# LED_bars.net
KiCad netlist of a schematic drawn in Altium Designer
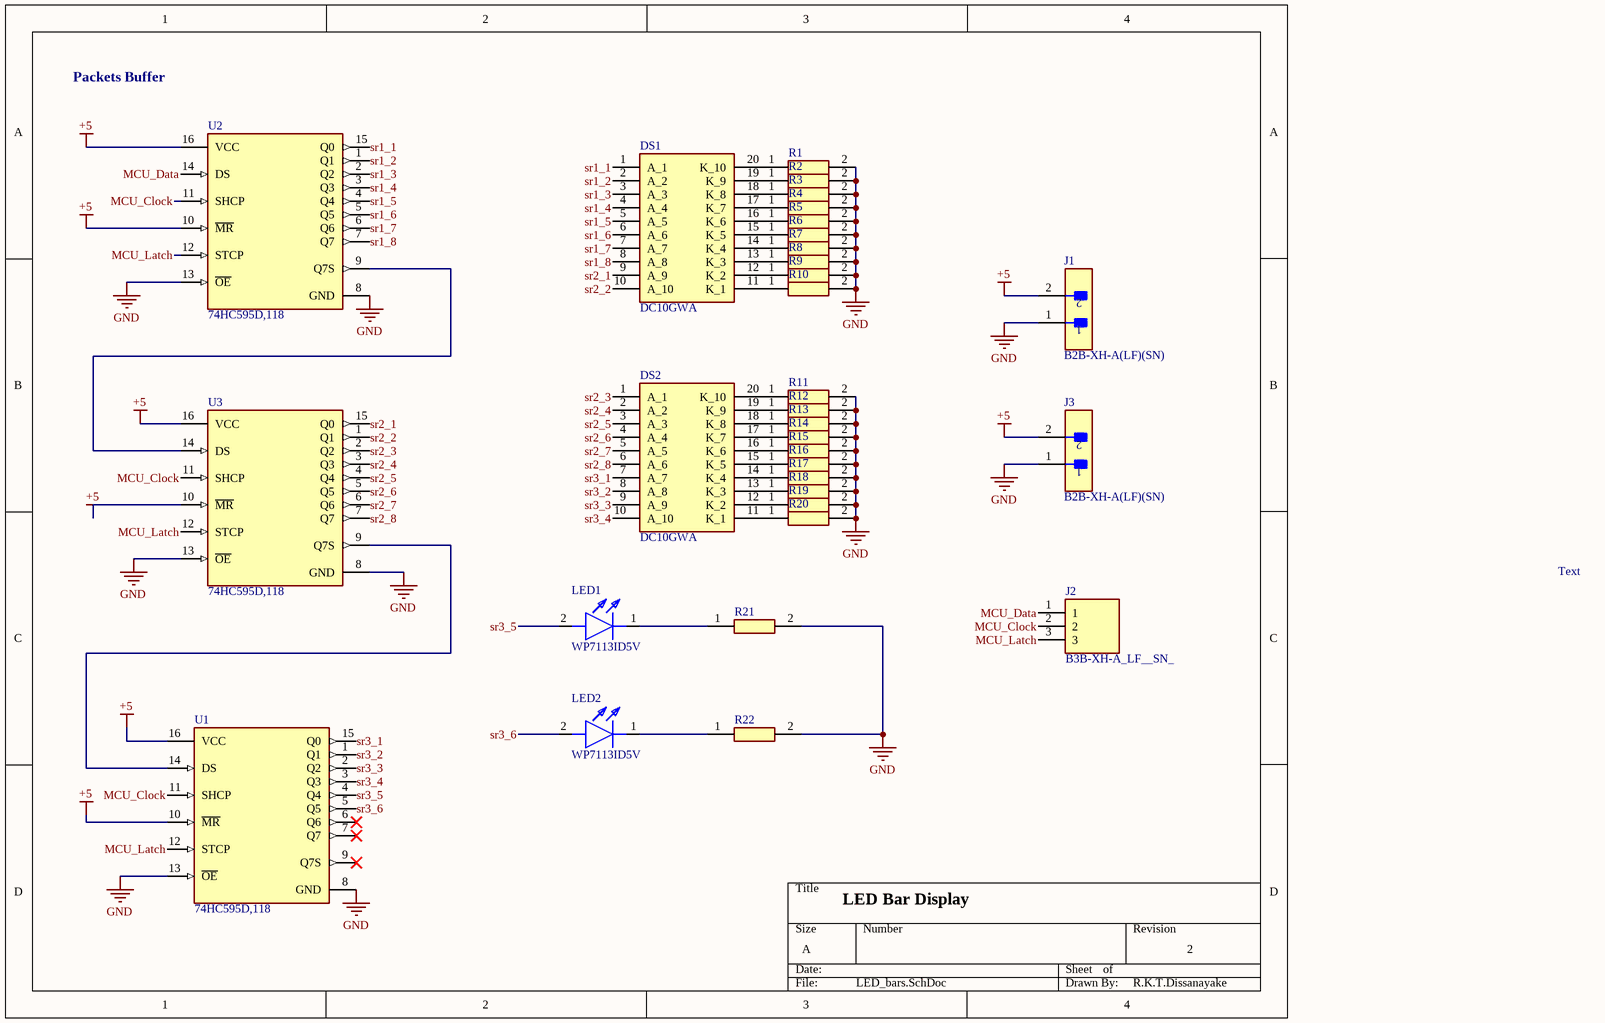
[diagram p0: LED_bars.SchDoc]

(export (version "E")
  (design (tool "Eeschema 10.0.6"))
  (components
    (comp (ref "DS1")
      (value "DC10GWA")
      (footprint "LED_Buffer:DIPS750W75P254L2540H825Q20N")
      (description "Display")
      (fields (field (name "MOUSER PART NUMBER") "604-DC10GWA"))
      (libsource (lib "*") (part "DC10GWA"))
    )
    (comp (ref "DS2")
      (value "DC10GWA")
      (footprint "LED_Buffer:DIPS750W75P254L2540H825Q20N")
      (description "Display")
      (fields (field (name "MOUSER PART NUMBER") "604-DC10GWA"))
      (libsource (lib "*") (part "DC10GWA"))
    )
    (comp (ref "J1")
      (value "B2B-XH-A(LF)(SN)")
      (footprint "FP-B2B-XH-A_LF_SN-MFG")
      (description "CONN HEADER VERT 2POS 2.5MM")
      (libsource (lib "Altium Content Vault") (part "3bc925449376181038e59eaffc5286c"))
    )
    (comp (ref "J2")
      (value "B3B-XH-A_LF__SN_")
      (footprint "LED_Buffer:B3BXHALFSN")
      (description "Connector")
      (fields
        (field (name "MANUFACTURER_PART_NUMBER") "B3B-XH-A(LF)(SN)")
        (field (name "MOUSER PART NUMBER") "306-B3BXHALFSNP")
      )
      (libsource (lib "*") (part "B3B-XH-A_LF__SN_"))
    )
    (comp (ref "J3")
      (value "B2B-XH-A(LF)(SN)")
      (footprint "FP-B2B-XH-A_LF_SN-MFG")
      (description "CONN HEADER VERT 2POS 2.5MM")
      (libsource (lib "Altium Content Vault") (part "3bc925449376181038e59eaffc5286c"))
    )
    (comp (ref "LED1")
      (value "WP7113ID5V")
      (footprint "LED_TwoBars:WP7113ID5V")
      (description "LED")
      (fields (field (name "MOUSER PART NUMBER") "604-WP7113ID5V"))
      (libsource (lib "*") (part "WP7113ID5V"))
    )
    (comp (ref "LED2")
      (value "WP7113ID5V")
      (footprint "LED_TwoBars:WP7113ID5V")
      (description "LED")
      (fields (field (name "MOUSER PART NUMBER") "604-WP7113ID5V"))
      (libsource (lib "*") (part "WP7113ID5V"))
    )
    (comp (ref "R1")
      (value "330")
      (footprint "LED_Buffer:RESC3126X65N")
      (description "Resistor")
      (fields (field (name "MANUFACTURER_PART_NUMBER") "RC1210FR-07330RL"))
      (libsource (lib "*") (part "RC1210FR-07330RL"))
    )
    (comp (ref "R2")
      (value "RC1210FR-07330RL")
      (footprint "LED_Buffer:RESC3126X65N")
      (description "Resistor")
      (libsource (lib "*") (part "RC1210FR-07330RL"))
    )
    (comp (ref "R3")
      (value "330")
      (footprint "LED_Buffer:RESC3126X65N")
      (description "Resistor")
      (fields (field (name "MANUFACTURER_PART_NUMBER") "RC1210FR-07330RL"))
      (libsource (lib "*") (part "RC1210FR-07330RL"))
    )
    (comp (ref "R4")
      (value "RC1210FR-07330RL")
      (footprint "LED_Buffer:RESC3126X65N")
      (description "Resistor")
      (libsource (lib "*") (part "RC1210FR-07330RL"))
    )
    (comp (ref "R5")
      (value "330")
      (footprint "LED_Buffer:RESC3126X65N")
      (description "Resistor")
      (fields (field (name "MANUFACTURER_PART_NUMBER") "RC1210FR-07330RL"))
      (libsource (lib "*") (part "RC1210FR-07330RL"))
    )
    (comp (ref "R6")
      (value "RC1210FR-07330RL")
      (footprint "LED_Buffer:RESC3126X65N")
      (description "Resistor")
      (libsource (lib "*") (part "RC1210FR-07330RL"))
    )
    (comp (ref "R7")
      (value "330")
      (footprint "LED_Buffer:RESC3126X65N")
      (description "Resistor")
      (fields (field (name "MANUFACTURER_PART_NUMBER") "RC1210FR-07330RL"))
      (libsource (lib "*") (part "RC1210FR-07330RL"))
    )
    (comp (ref "R8")
      (value "RC1210FR-07330RL")
      (footprint "LED_Buffer:RESC3126X65N")
      (description "Resistor")
      (libsource (lib "*") (part "RC1210FR-07330RL"))
    )
    (comp (ref "R9")
      (value "330")
      (footprint "LED_Buffer:RESC3126X65N")
      (description "Resistor")
      (fields (field (name "MANUFACTURER_PART_NUMBER") "RC1210FR-07330RL"))
      (libsource (lib "*") (part "RC1210FR-07330RL"))
    )
    (comp (ref "R10")
      (value "330")
      (footprint "LED_Buffer:RESC3126X65N")
      (description "Resistor")
      (fields (field (name "MANUFACTURER_PART_NUMBER") "RC1210FR-07330RL"))
      (libsource (lib "*") (part "RC1210FR-07330RL"))
    )
    (comp (ref "R11")
      (value "330")
      (footprint "LED_Buffer:RESC3126X65N")
      (description "Resistor")
      (fields (field (name "MANUFACTURER_PART_NUMBER") "RC1210FR-07330RL"))
      (libsource (lib "*") (part "RC1210FR-07330RL"))
    )
    (comp (ref "R12")
      (value "330")
      (footprint "LED_Buffer:RESC3126X65N")
      (description "Resistor")
      (fields (field (name "MANUFACTURER_PART_NUMBER") "RC1210FR-07330RL"))
      (libsource (lib "*") (part "RC1210FR-07330RL"))
    )
    (comp (ref "R13")
      (value "330")
      (footprint "LED_Buffer:RESC3126X65N")
      (description "Resistor")
      (fields (field (name "MANUFACTURER_PART_NUMBER") "RC1210FR-07330RL"))
      (libsource (lib "*") (part "RC1210FR-07330RL"))
    )
    (comp (ref "R14")
      (value "330")
      (footprint "LED_Buffer:RESC3126X65N")
      (description "Resistor")
      (fields (field (name "MANUFACTURER_PART_NUMBER") "RC1210FR-07330RL"))
      (libsource (lib "*") (part "RC1210FR-07330RL"))
    )
    (comp (ref "R15")
      (value "330")
      (footprint "LED_Buffer:RESC3126X65N")
      (description "Resistor")
      (fields (field (name "MANUFACTURER_PART_NUMBER") "RC1210FR-07330RL"))
      (libsource (lib "*") (part "RC1210FR-07330RL"))
    )
    (comp (ref "R16")
      (value "330")
      (footprint "LED_Buffer:RESC3126X65N")
      (description "Resistor")
      (fields (field (name "MANUFACTURER_PART_NUMBER") "RC1210FR-07330RL"))
      (libsource (lib "*") (part "RC1210FR-07330RL"))
    )
    (comp (ref "R17")
      (value "330")
      (footprint "LED_Buffer:RESC3126X65N")
      (description "Resistor")
      (fields (field (name "MANUFACTURER_PART_NUMBER") "RC1210FR-07330RL"))
      (libsource (lib "*") (part "RC1210FR-07330RL"))
    )
    (comp (ref "R18")
      (value "330")
      (footprint "LED_Buffer:RESC3126X65N")
      (description "Resistor")
      (fields (field (name "MANUFACTURER_PART_NUMBER") "RC1210FR-07330RL"))
      (libsource (lib "*") (part "RC1210FR-07330RL"))
    )
    (comp (ref "R19")
      (value "RC1210FR-07330RL")
      (footprint "LED_Buffer:RESC3126X65N")
      (description "Resistor")
      (libsource (lib "*") (part "RC1210FR-07330RL"))
    )
    (comp (ref "R20")
      (value "330")
      (footprint "LED_Buffer:RESC3126X65N")
      (description "Resistor")
      (fields (field (name "MANUFACTURER_PART_NUMBER") "RC1210FR-07330RL"))
      (libsource (lib "*") (part "RC1210FR-07330RL"))
    )
    (comp (ref "R21")
      (value "330")
      (footprint "LED_Buffer:RESC3126X65N")
      (description "Resistor")
      (fields (field (name "MANUFACTURER_PART_NUMBER") "RC1210FR-07330RL"))
      (libsource (lib "*") (part "RC1210FR-07330RL"))
    )
    (comp (ref "R22")
      (value "330")
      (footprint "LED_Buffer:RESC3126X65N")
      (description "Resistor")
      (fields (field (name "MANUFACTURER_PART_NUMBER") "RC1210FR-07330RL"))
      (libsource (lib "*") (part "RC1210FR-07330RL"))
    )
    (comp (ref "U1")
      (value "74HC595D,118")
      (footprint "FP-SOT109-1-IPC_C")
      (description "IC SHIFT REGISTER 8BIT 16SOIC")
      (libsource (lib "Altium Content Vault") (part "7b153f231cfcc3ac06dee253bd56617"))
    )
    (comp (ref "U2")
      (value "74HC595D,118")
      (footprint "FP-SOT109-1-IPC_C")
      (description "IC SHIFT REGISTER 8BIT 16SOIC")
      (libsource (lib "Altium Content Vault") (part "7b153f231cfcc3ac06dee253bd56617"))
    )
    (comp (ref "U3")
      (value "74HC595D,118")
      (footprint "FP-SOT109-1-IPC_C")
      (description "IC SHIFT REGISTER 8BIT 16SOIC")
      (libsource (lib "Altium Content Vault") (part "7b153f231cfcc3ac06dee253bd56617"))
    )
  )
  (nets
    (net (code "1") (name "+5") (class "Default")
      (node (ref "J1") (pin "2") (pinfunction "2_2") (pintype "passive"))
      (node (ref "J3") (pin "2") (pinfunction "2_2") (pintype "passive"))
      (node (ref "U1") (pin "10") (pinfunction "~{MR}_10") (pintype "input"))
      (node (ref "U1") (pin "16") (pinfunction "VCC_16") (pintype "power_in"))
      (node (ref "U2") (pin "10") (pinfunction "~{MR}_10") (pintype "input"))
      (node (ref "U2") (pin "16") (pinfunction "VCC_16") (pintype "power_in"))
      (node (ref "U3") (pin "10") (pinfunction "~{MR}_10") (pintype "input"))
      (node (ref "U3") (pin "16") (pinfunction "VCC_16") (pintype "power_in"))
    )
    (net (code "2") (name "/MCU_Clock") (class "Default")
      (node (ref "J2") (pin "2") (pinfunction "2_2") (pintype "passive"))
      (node (ref "U1") (pin "11") (pinfunction "SHCP_11") (pintype "input"))
      (node (ref "U2") (pin "11") (pinfunction "SHCP_11") (pintype "input"))
      (node (ref "U3") (pin "11") (pinfunction "SHCP_11") (pintype "input"))
    )
    (net (code "3") (name "/MCU_Data") (class "Default")
      (node (ref "J2") (pin "1") (pinfunction "1_1") (pintype "passive"))
      (node (ref "U2") (pin "14") (pinfunction "DS_14") (pintype "input"))
    )
    (net (code "4") (name "/MCU_Latch") (class "Default")
      (node (ref "J2") (pin "3") (pinfunction "3_3") (pintype "passive"))
      (node (ref "U1") (pin "12") (pinfunction "STCP_12") (pintype "input"))
      (node (ref "U2") (pin "12") (pinfunction "STCP_12") (pintype "input"))
      (node (ref "U3") (pin "12") (pinfunction "STCP_12") (pintype "input"))
    )
    (net (code "5") (name "/sr1_1") (class "Default")
      (node (ref "DS1") (pin "1") (pinfunction "A_1_1") (pintype "passive"))
      (node (ref "U2") (pin "15") (pinfunction "Q0_15") (pintype "output"))
    )
    (net (code "6") (name "/sr1_2") (class "Default")
      (node (ref "DS1") (pin "2") (pinfunction "A_2_2") (pintype "passive"))
      (node (ref "U2") (pin "1") (pinfunction "Q1_1") (pintype "output"))
    )
    (net (code "7") (name "/sr1_3") (class "Default")
      (node (ref "DS1") (pin "3") (pinfunction "A_3_3") (pintype "passive"))
      (node (ref "U2") (pin "2") (pinfunction "Q2_2") (pintype "output"))
    )
    (net (code "8") (name "/sr1_4") (class "Default")
      (node (ref "DS1") (pin "4") (pinfunction "A_4_4") (pintype "passive"))
      (node (ref "U2") (pin "3") (pinfunction "Q3_3") (pintype "output"))
    )
    (net (code "9") (name "/sr1_5") (class "Default")
      (node (ref "DS1") (pin "5") (pinfunction "A_5_5") (pintype "passive"))
      (node (ref "U2") (pin "4") (pinfunction "Q4_4") (pintype "output"))
    )
    (net (code "10") (name "/sr1_6") (class "Default")
      (node (ref "DS1") (pin "6") (pinfunction "A_6_6") (pintype "passive"))
      (node (ref "U2") (pin "5") (pinfunction "Q5_5") (pintype "output"))
    )
    (net (code "11") (name "/sr1_7") (class "Default")
      (node (ref "DS1") (pin "7") (pinfunction "A_7_7") (pintype "passive"))
      (node (ref "U2") (pin "6") (pinfunction "Q6_6") (pintype "output"))
    )
    (net (code "12") (name "/sr1_8") (class "Default")
      (node (ref "DS1") (pin "8") (pinfunction "A_8_8") (pintype "passive"))
      (node (ref "U2") (pin "7") (pinfunction "Q7_7") (pintype "output"))
    )
    (net (code "13") (name "/sr2_1") (class "Default")
      (node (ref "DS1") (pin "9") (pinfunction "A_9_9") (pintype "passive"))
      (node (ref "U3") (pin "15") (pinfunction "Q0_15") (pintype "output"))
    )
    (net (code "14") (name "/sr2_2") (class "Default")
      (node (ref "DS1") (pin "10") (pinfunction "A_10_10") (pintype "passive"))
      (node (ref "U3") (pin "1") (pinfunction "Q1_1") (pintype "output"))
    )
    (net (code "15") (name "/sr2_3") (class "Default")
      (node (ref "DS2") (pin "1") (pinfunction "A_1_1") (pintype "passive"))
      (node (ref "U3") (pin "2") (pinfunction "Q2_2") (pintype "output"))
    )
    (net (code "16") (name "/sr2_4") (class "Default")
      (node (ref "DS2") (pin "2") (pinfunction "A_2_2") (pintype "passive"))
      (node (ref "U3") (pin "3") (pinfunction "Q3_3") (pintype "output"))
    )
    (net (code "17") (name "/sr2_5") (class "Default")
      (node (ref "DS2") (pin "3") (pinfunction "A_3_3") (pintype "passive"))
      (node (ref "U3") (pin "4") (pinfunction "Q4_4") (pintype "output"))
    )
    (net (code "18") (name "/sr2_6") (class "Default")
      (node (ref "DS2") (pin "4") (pinfunction "A_4_4") (pintype "passive"))
      (node (ref "U3") (pin "5") (pinfunction "Q5_5") (pintype "output"))
    )
    (net (code "19") (name "/sr2_7") (class "Default")
      (node (ref "DS2") (pin "5") (pinfunction "A_5_5") (pintype "passive"))
      (node (ref "U3") (pin "6") (pinfunction "Q6_6") (pintype "output"))
    )
    (net (code "20") (name "/sr2_8") (class "Default")
      (node (ref "DS2") (pin "6") (pinfunction "A_6_6") (pintype "passive"))
      (node (ref "U3") (pin "7") (pinfunction "Q7_7") (pintype "output"))
    )
    (net (code "21") (name "/sr3_1") (class "Default")
      (node (ref "DS2") (pin "7") (pinfunction "A_7_7") (pintype "passive"))
      (node (ref "U1") (pin "15") (pinfunction "Q0_15") (pintype "output"))
    )
    (net (code "22") (name "/sr3_2") (class "Default")
      (node (ref "DS2") (pin "8") (pinfunction "A_8_8") (pintype "passive"))
      (node (ref "U1") (pin "1") (pinfunction "Q1_1") (pintype "output"))
    )
    (net (code "23") (name "/sr3_3") (class "Default")
      (node (ref "DS2") (pin "9") (pinfunction "A_9_9") (pintype "passive"))
      (node (ref "U1") (pin "2") (pinfunction "Q2_2") (pintype "output"))
    )
    (net (code "24") (name "/sr3_4") (class "Default")
      (node (ref "DS2") (pin "10") (pinfunction "A_10_10") (pintype "passive"))
      (node (ref "U1") (pin "3") (pinfunction "Q3_3") (pintype "output"))
    )
    (net (code "25") (name "/sr3_5") (class "Default")
      (node (ref "LED1") (pin "2") (pinfunction "A_2") (pintype "passive"))
      (node (ref "U1") (pin "4") (pinfunction "Q4_4") (pintype "output"))
    )
    (net (code "26") (name "/sr3_6") (class "Default")
      (node (ref "LED2") (pin "2") (pinfunction "A_2") (pintype "passive"))
      (node (ref "U1") (pin "5") (pinfunction "Q5_5") (pintype "output"))
    )
    (net (code "27") (name "GND") (class "Default")
      (node (ref "J1") (pin "1") (pinfunction "1_1") (pintype "passive"))
      (node (ref "J3") (pin "1") (pinfunction "1_1") (pintype "passive"))
      (node (ref "R1") (pin "2") (pinfunction "2_2") (pintype "passive"))
      (node (ref "R10") (pin "2") (pinfunction "2_2") (pintype "passive"))
      (node (ref "R11") (pin "2") (pinfunction "2_2") (pintype "passive"))
      (node (ref "R12") (pin "2") (pinfunction "2_2") (pintype "passive"))
      (node (ref "R13") (pin "2") (pinfunction "2_2") (pintype "passive"))
      (node (ref "R14") (pin "2") (pinfunction "2_2") (pintype "passive"))
      (node (ref "R15") (pin "2") (pinfunction "2_2") (pintype "passive"))
      (node (ref "R16") (pin "2") (pinfunction "2_2") (pintype "passive"))
      (node (ref "R17") (pin "2") (pinfunction "2_2") (pintype "passive"))
      (node (ref "R18") (pin "2") (pinfunction "2_2") (pintype "passive"))
      (node (ref "R19") (pin "2") (pinfunction "2_2") (pintype "passive"))
      (node (ref "R2") (pin "2") (pinfunction "2_2") (pintype "passive"))
      (node (ref "R20") (pin "2") (pinfunction "2_2") (pintype "passive"))
      (node (ref "R21") (pin "2") (pinfunction "2_2") (pintype "passive"))
      (node (ref "R22") (pin "2") (pinfunction "2_2") (pintype "passive"))
      (node (ref "R3") (pin "2") (pinfunction "2_2") (pintype "passive"))
      (node (ref "R4") (pin "2") (pinfunction "2_2") (pintype "passive"))
      (node (ref "R5") (pin "2") (pinfunction "2_2") (pintype "passive"))
      (node (ref "R6") (pin "2") (pinfunction "2_2") (pintype "passive"))
      (node (ref "R7") (pin "2") (pinfunction "2_2") (pintype "passive"))
      (node (ref "R8") (pin "2") (pinfunction "2_2") (pintype "passive"))
      (node (ref "R9") (pin "2") (pinfunction "2_2") (pintype "passive"))
      (node (ref "U1") (pin "13") (pinfunction "~{OE}_13") (pintype "input"))
      (node (ref "U1") (pin "8") (pinfunction "GND_8") (pintype "power_in"))
      (node (ref "U2") (pin "13") (pinfunction "~{OE}_13") (pintype "input"))
      (node (ref "U2") (pin "8") (pinfunction "GND_8") (pintype "power_in"))
      (node (ref "U3") (pin "13") (pinfunction "~{OE}_13") (pintype "input"))
      (node (ref "U3") (pin "8") (pinfunction "GND_8") (pintype "power_in"))
    )
    (net (code "28") (name "Net-(DS1-K_1)") (class "Default")
      (node (ref "DS1") (pin "11") (pinfunction "K_1_11") (pintype "passive"))
      (node (ref "R10") (pin "1") (pinfunction "1_1") (pintype "passive"))
    )
    (net (code "29") (name "Net-(DS1-K_2)") (class "Default")
      (node (ref "DS1") (pin "12") (pinfunction "K_2_12") (pintype "passive"))
      (node (ref "R9") (pin "1") (pinfunction "1_1") (pintype "passive"))
    )
    (net (code "30") (name "Net-(DS1-K_3)") (class "Default")
      (node (ref "DS1") (pin "13") (pinfunction "K_3_13") (pintype "passive"))
      (node (ref "R8") (pin "1") (pinfunction "1_1") (pintype "passive"))
    )
    (net (code "31") (name "Net-(DS1-K_4)") (class "Default")
      (node (ref "DS1") (pin "14") (pinfunction "K_4_14") (pintype "passive"))
      (node (ref "R7") (pin "1") (pinfunction "1_1") (pintype "passive"))
    )
    (net (code "32") (name "Net-(DS1-K_5)") (class "Default")
      (node (ref "DS1") (pin "15") (pinfunction "K_5_15") (pintype "passive"))
      (node (ref "R6") (pin "1") (pinfunction "1_1") (pintype "passive"))
    )
    (net (code "33") (name "Net-(DS1-K_6)") (class "Default")
      (node (ref "DS1") (pin "16") (pinfunction "K_6_16") (pintype "passive"))
      (node (ref "R5") (pin "1") (pinfunction "1_1") (pintype "passive"))
    )
    (net (code "34") (name "Net-(DS1-K_7)") (class "Default")
      (node (ref "DS1") (pin "17") (pinfunction "K_7_17") (pintype "passive"))
      (node (ref "R4") (pin "1") (pinfunction "1_1") (pintype "passive"))
    )
    (net (code "35") (name "Net-(DS1-K_8)") (class "Default")
      (node (ref "DS1") (pin "18") (pinfunction "K_8_18") (pintype "passive"))
      (node (ref "R3") (pin "1") (pinfunction "1_1") (pintype "passive"))
    )
    (net (code "36") (name "Net-(DS1-K_9)") (class "Default")
      (node (ref "DS1") (pin "19") (pinfunction "K_9_19") (pintype "passive"))
      (node (ref "R2") (pin "1") (pinfunction "1_1") (pintype "passive"))
    )
    (net (code "37") (name "Net-(DS1-K_10)") (class "Default")
      (node (ref "DS1") (pin "20") (pinfunction "K_10_20") (pintype "passive"))
      (node (ref "R1") (pin "1") (pinfunction "1_1") (pintype "passive"))
    )
    (net (code "38") (name "Net-(DS2-K_1)") (class "Default")
      (node (ref "DS2") (pin "11") (pinfunction "K_1_11") (pintype "passive"))
      (node (ref "R20") (pin "1") (pinfunction "1_1") (pintype "passive"))
    )
    (net (code "39") (name "Net-(DS2-K_2)") (class "Default")
      (node (ref "DS2") (pin "12") (pinfunction "K_2_12") (pintype "passive"))
      (node (ref "R19") (pin "1") (pinfunction "1_1") (pintype "passive"))
    )
    (net (code "40") (name "Net-(DS2-K_3)") (class "Default")
      (node (ref "DS2") (pin "13") (pinfunction "K_3_13") (pintype "passive"))
      (node (ref "R18") (pin "1") (pinfunction "1_1") (pintype "passive"))
    )
    (net (code "41") (name "Net-(DS2-K_4)") (class "Default")
      (node (ref "DS2") (pin "14") (pinfunction "K_4_14") (pintype "passive"))
      (node (ref "R17") (pin "1") (pinfunction "1_1") (pintype "passive"))
    )
    (net (code "42") (name "Net-(DS2-K_5)") (class "Default")
      (node (ref "DS2") (pin "15") (pinfunction "K_5_15") (pintype "passive"))
      (node (ref "R16") (pin "1") (pinfunction "1_1") (pintype "passive"))
    )
    (net (code "43") (name "Net-(DS2-K_6)") (class "Default")
      (node (ref "DS2") (pin "16") (pinfunction "K_6_16") (pintype "passive"))
      (node (ref "R15") (pin "1") (pinfunction "1_1") (pintype "passive"))
    )
    (net (code "44") (name "Net-(DS2-K_7)") (class "Default")
      (node (ref "DS2") (pin "17") (pinfunction "K_7_17") (pintype "passive"))
      (node (ref "R14") (pin "1") (pinfunction "1_1") (pintype "passive"))
    )
    (net (code "45") (name "Net-(DS2-K_8)") (class "Default")
      (node (ref "DS2") (pin "18") (pinfunction "K_8_18") (pintype "passive"))
      (node (ref "R13") (pin "1") (pinfunction "1_1") (pintype "passive"))
    )
    (net (code "46") (name "Net-(DS2-K_9)") (class "Default")
      (node (ref "DS2") (pin "19") (pinfunction "K_9_19") (pintype "passive"))
      (node (ref "R12") (pin "1") (pinfunction "1_1") (pintype "passive"))
    )
    (net (code "47") (name "Net-(DS2-K_10)") (class "Default")
      (node (ref "DS2") (pin "20") (pinfunction "K_10_20") (pintype "passive"))
      (node (ref "R11") (pin "1") (pinfunction "1_1") (pintype "passive"))
    )
    (net (code "48") (name "Net-(LED1-K)") (class "Default")
      (node (ref "LED1") (pin "1") (pinfunction "K_1") (pintype "passive"))
      (node (ref "R21") (pin "1") (pinfunction "1_1") (pintype "passive"))
    )
    (net (code "49") (name "Net-(LED2-K)") (class "Default")
      (node (ref "LED2") (pin "1") (pinfunction "K_1") (pintype "passive"))
      (node (ref "R22") (pin "1") (pinfunction "1_1") (pintype "passive"))
    )
    (net (code "50") (name "Net-(U1-DS)") (class "Default")
      (node (ref "U1") (pin "14") (pinfunction "DS_14") (pintype "input"))
      (node (ref "U3") (pin "9") (pinfunction "Q7S_9") (pintype "output"))
    )
    (net (code "51") (name "Net-(U2-Q7S)") (class "Default")
      (node (ref "U2") (pin "9") (pinfunction "Q7S_9") (pintype "output"))
      (node (ref "U3") (pin "14") (pinfunction "DS_14") (pintype "input"))
    )
    (net (code "52") (name "unconnected-(U1-Q6-Pad6)") (class "Default")
      (node (ref "U1") (pin "6") (pinfunction "Q6_6") (pintype "output+no_connect"))
    )
    (net (code "53") (name "unconnected-(U1-Q7-Pad7)") (class "Default")
      (node (ref "U1") (pin "7") (pinfunction "Q7_7") (pintype "output+no_connect"))
    )
    (net (code "54") (name "unconnected-(U1-Q7S-Pad9)") (class "Default")
      (node (ref "U1") (pin "9") (pinfunction "Q7S_9") (pintype "output+no_connect"))
    )
  )
)
